# ESC.net
KiCad netlist of a schematic drawn in Altium Designer
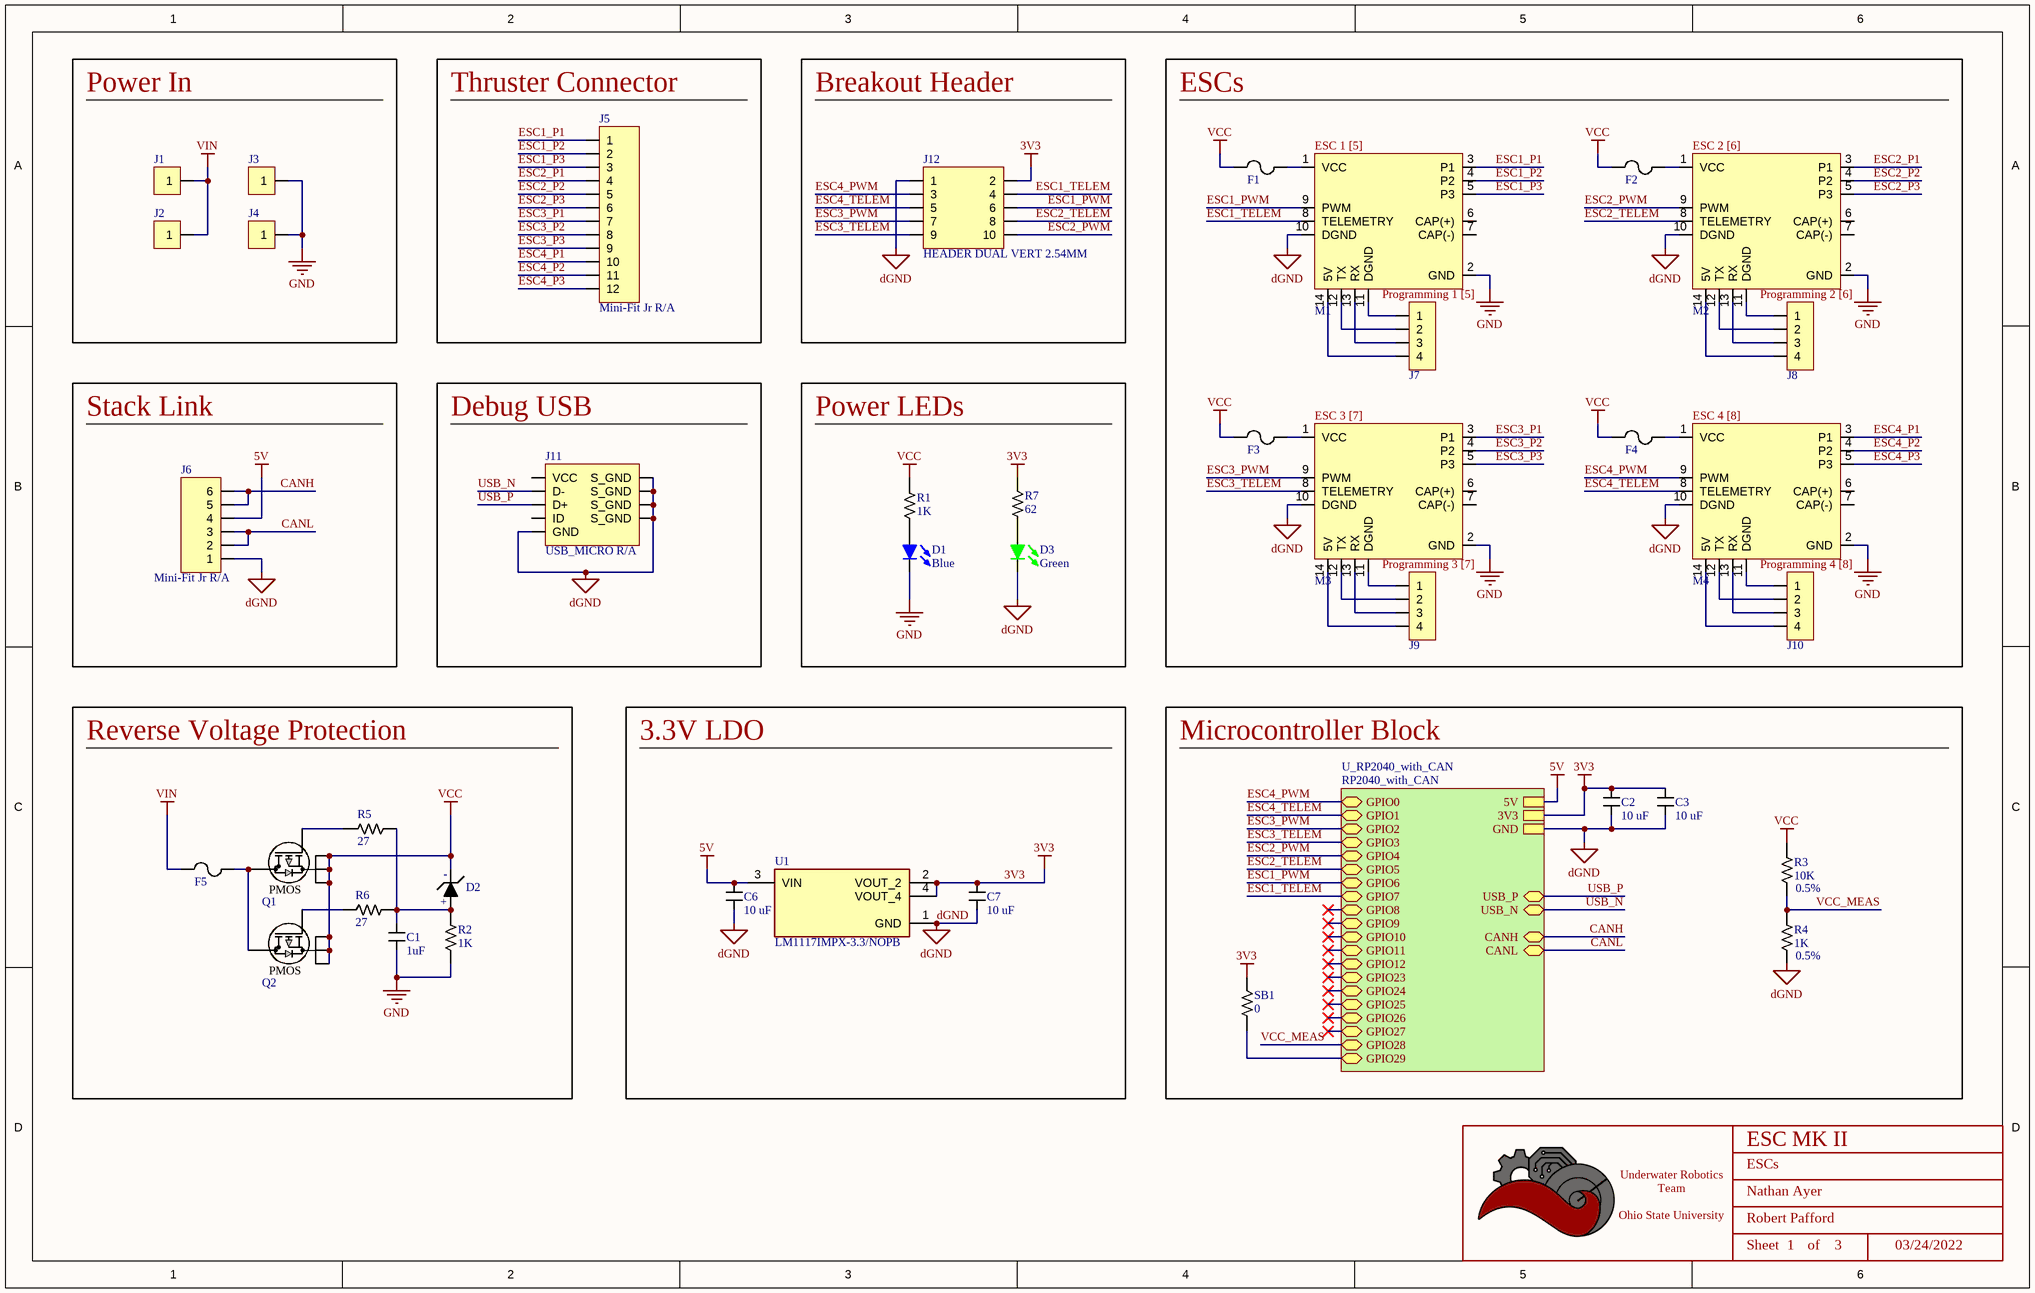
[diagram p0: ESC.SchDoc]

(export (version "E")
  (design (tool "Eeschema 10.0.6"))
  (components
    (comp (ref "*")
      (value "Title_Block")
      (footprint "LOGO")
      (description "UWRT Schematic Title Block Template\r\n\r\nCreated June 2021, Dylan Trainor")
      (libsource (lib "UWRT") (part "Title_Block"))
    )
    (comp (ref "C1")
      (value "1uF")
      (footprint "CAPACITOR_0603")
      (description "Cap 1uF 16V +/-10%\r\nCeramic 0603")
      (fields
        (field (name "TOLERANCE") "+/- 10%")
        (field (name "VOLTAGE") "16V")
        (field (name "MADE BY") "Flip B")
      )
      (libsource (lib "Capacitors") (part "CAPACITOR_1uF_0603"))
    )
    (comp (ref "C2")
      (value "10uF Ceramic 6.3V")
      (footprint "CAPACITOR_0603")
      (description "Cap 10uF 6.3V +/-20%\r\nCeramic 0603")
      (fields
        (field (name "TOLERANCE") "+/- 20%")
        (field (name "VOLTAGE") "6.3V")
        (field (name "VALUE (UF)") "10 uF")
        (field (name "MADE BY") "Flip B")
      )
      (libsource (lib "Capacitors") (part "CAPACITOR_10uF_0603"))
    )
    (comp (ref "C3")
      (value "10uF Ceramic 6.3V")
      (footprint "CAPACITOR_0603")
      (description "Cap 10uF 6.3V +/-20%\r\nCeramic 0603")
      (fields
        (field (name "TOLERANCE") "+/- 20%")
        (field (name "VOLTAGE") "6.3V")
        (field (name "VALUE (UF)") "10 uF")
        (field (name "MADE BY") "Flip B")
      )
      (libsource (lib "Capacitors") (part "CAPACITOR_10uF_0603"))
    )
    (comp (ref "C6")
      (value "10uF Ceramic 6.3V")
      (footprint "CAPACITOR_0603")
      (description "Cap 10uF 6.3V +/-20%\r\nCeramic 0603")
      (fields
        (field (name "TOLERANCE") "+/- 20%")
        (field (name "VOLTAGE") "6.3V")
        (field (name "VALUE (UF)") "10 uF")
        (field (name "MADE BY") "Flip B")
      )
      (libsource (lib "Capacitors") (part "CAPACITOR_10uF_0603"))
    )
    (comp (ref "C7")
      (value "10uF Ceramic 6.3V")
      (footprint "CAPACITOR_0603")
      (description "Cap 10uF 6.3V +/-20%\r\nCeramic 0603")
      (fields
        (field (name "TOLERANCE") "+/- 20%")
        (field (name "VOLTAGE") "6.3V")
        (field (name "VALUE (UF)") "10 uF")
        (field (name "MADE BY") "Flip B")
      )
      (libsource (lib "Capacitors") (part "CAPACITOR_10uF_0603"))
    )
    (comp (ref "D1")
      (value "150060BS75000")
      (footprint "LED_0603")
      (description "LED Blue Vf= 3.2V If = 0.020A\r\n150060BS75000")
      (fields (field (name "COLOR") "Blue") (field (name "MADE BY") "Robert Pafford"))
      (libsource (lib "Diodes") (part "LED_Blue_0603"))
    )
    (comp (ref "D2")
      (value "Zener_Diode_10V_410mW")
      (footprint "SOD-123")
      (description "Zener Diode ¦ 10 V ¦ 410 mW ¦ SOD 123")
      (fields (field (name "POWER") "410mW") (field (name "MADE BY") "Nathan A"))
      (libsource (lib "Diodes") (part "Zener_Diode_10V_410mW"))
    )
    (comp (ref "D3")
      (value "150060GS75000")
      (footprint "LED_0603")
      (description "LED Green Vf= 3.2V If = 0.025A\r\n150060GS75000")
      (fields (field (name "COLOR") "Green") (field (name "MADE BY") "Flip B"))
      (libsource (lib "Diodes") (part "LED_Green_0603_3.2V"))
    )
    (comp (ref "F1")
      (value "0685H9150-01")
      (footprint "0501Series_LTF")
      (description "Bel Fuse  ¦ 15A ¦ 32V DC ¦ SMD ¦ Fast Blow ¦ 1206")
      (fields (field (name "CREATED BY") "Nathan Ayer"))
      (libsource (lib "Fuses") (part "Bel Fuse 15A"))
    )
    (comp (ref "F2")
      (value "0685H9150-01")
      (footprint "0501Series_LTF")
      (description "Bel Fuse  ¦ 15A ¦ 32V DC ¦ SMD ¦ Fast Blow ¦ 1206")
      (fields (field (name "CREATED BY") "Nathan Ayer"))
      (libsource (lib "Fuses") (part "Bel Fuse 15A"))
    )
    (comp (ref "F3")
      (value "0685H9150-01")
      (footprint "0501Series_LTF")
      (description "Bel Fuse  ¦ 15A ¦ 32V DC ¦ SMD ¦ Fast Blow ¦ 1206")
      (fields (field (name "CREATED BY") "Nathan Ayer"))
      (libsource (lib "Fuses") (part "Bel Fuse 15A"))
    )
    (comp (ref "F4")
      (value "0685H9150-01")
      (footprint "0501Series_LTF")
      (description "Bel Fuse  ¦ 15A ¦ 32V DC ¦ SMD ¦ Fast Blow ¦ 1206")
      (fields (field (name "CREATED BY") "Nathan Ayer"))
      (libsource (lib "Fuses") (part "Bel Fuse 15A"))
    )
    (comp (ref "F5")
      (value "1245HC60-RTR")
      (footprint "2-SMD Fuse")
      (description "Eaton  ¦ 60A ¦ 80V DC ¦ SMD ¦ Fast Blow ¦ 2-SMD")
      (fields (field (name "CREATED BY") "Nathan Ayer"))
      (libsource (lib "Fuses") (part "Eaton 60A Fuse"))
    )
    (comp (ref "J1")
      (value "Redcube M4 Term 85A")
      (footprint "Redcube M4 Term 85A")
      (fields (field (name "CREATED BY") "Nahtan Ayer"))
      (libsource (lib "Connectors") (part "Redcube M4 Term 85A"))
    )
    (comp (ref "J2")
      (value "Redcube M4 Term 85A")
      (footprint "Redcube M4 Term 85A")
      (fields (field (name "CREATED BY") "Nahtan Ayer"))
      (libsource (lib "Connectors") (part "Redcube M4 Term 85A"))
    )
    (comp (ref "J3")
      (value "Redcube M4 Term 85A")
      (footprint "Redcube M4 Term 85A")
      (fields (field (name "CREATED BY") "Nahtan Ayer"))
      (libsource (lib "Connectors") (part "Redcube M4 Term 85A"))
    )
    (comp (ref "J4")
      (value "Redcube M4 Term 85A")
      (footprint "Redcube M4 Term 85A")
      (fields (field (name "CREATED BY") "Nahtan Ayer"))
      (libsource (lib "Connectors") (part "Redcube M4 Term 85A"))
    )
    (comp (ref "J5")
      (value "Mini-Fit Jr R/A")
      (footprint "CONN_MOLEX_MINIFIT JR_12 POS_R/A")
      (description "Molex Minifit Jr. 5569 \r\n12 Pos R/A Natural")
      (fields (field (name "MANUFACTURER") "Molex") (field (name "CREATED BY") "Flip B"))
      (libsource (lib "Connectors") (part "CONN_MOLEX_MINIFIT JR_12POS_R/A"))
    )
    (comp (ref "J6")
      (value "Mini-Fit Jr R/A")
      (footprint "CONN_MOLEX_MINIFIT JR_6 POS_R/A")
      (description "Molex Minifit Jr. 5569 \r\n6 Pos R/A Natural")
      (fields (field (name "MANUFACTURER") "Molex") (field (name "CREATED BY") "Flip B"))
      (libsource (lib "Connectors") (part "CONN_MOLEX_MINIFIT JR_6POS_R/A"))
    )
    (comp (ref "J7")
      (value "HEADER VERT 2.54MM")
      (footprint "HEADER_4PIN_2.54MM")
      (description "CONN HEADER VERT 4POS 2.54MM")
      (fields (field (name "MADE BY") "Robert Pafford"))
      (libsource (lib "Connectors") (part "HEADER_4PIN_2.54MM"))
    )
    (comp (ref "J8")
      (value "HEADER VERT 2.54MM")
      (footprint "HEADER_4PIN_2.54MM")
      (description "CONN HEADER VERT 4POS 2.54MM")
      (fields (field (name "MADE BY") "Robert Pafford"))
      (libsource (lib "Connectors") (part "HEADER_4PIN_2.54MM"))
    )
    (comp (ref "J9")
      (value "HEADER VERT 2.54MM")
      (footprint "HEADER_4PIN_2.54MM")
      (description "CONN HEADER VERT 4POS 2.54MM")
      (fields (field (name "MADE BY") "Robert Pafford"))
      (libsource (lib "Connectors") (part "HEADER_4PIN_2.54MM"))
    )
    (comp (ref "J10")
      (value "HEADER VERT 2.54MM")
      (footprint "HEADER_4PIN_2.54MM")
      (description "CONN HEADER VERT 4POS 2.54MM")
      (fields (field (name "MADE BY") "Robert Pafford"))
      (libsource (lib "Connectors") (part "HEADER_4PIN_2.54MM"))
    )
    (comp (ref "J11")
      (value "USB_MICRO R/A")
      (footprint "CONN_MINIUSB")
      (description "Amphenol Micro USB-B\r\nUSB2.0 5 Pin Right Angle SMD")
      (fields (field (name "MANUFACTURER") "Amphenol") (field (name "CREATED BY") "Flip B"))
      (libsource (lib "Connectors") (part "CONN_MICROUSB"))
    )
    (comp (ref "J12")
      (value "HEADER DUAL VERT 2.54MM")
      (footprint "HEADER_2X5PIN_2.54MM")
      (description "CONN HEADER VERT 10POS 2.54MM")
      (fields (field (name "MADE BY") "Robert Pafford"))
      (libsource (lib "Connectors") (part "HEADER_2x5PIN_2.54MM"))
    )
    (comp (ref "M1")
      (value "APD 80F3[X]")
      (footprint "APD 80F3[X]")
      (description "Advanced Power Drives 80F3[X] ESC ¦ 15-35V ¦ 80A")
      (fields
        (field (name "VOLTAGE") "15-35V")
        (field (name "MANUFACTURER") "Advanced Power Drives")
        (field (name "CREATED BY") "Nathan Ayer")
      )
      (libsource (lib "Modules") (part "APD 80F3[X]"))
    )
    (comp (ref "M2")
      (value "APD 80F3[X]")
      (footprint "APD 80F3[X]")
      (description "Advanced Power Drives 80F3[X] ESC ¦ 15-35V ¦ 80A")
      (fields
        (field (name "VOLTAGE") "15-35V")
        (field (name "MANUFACTURER") "Advanced Power Drives")
        (field (name "CREATED BY") "Nathan Ayer")
      )
      (libsource (lib "Modules") (part "APD 80F3[X]"))
    )
    (comp (ref "M3")
      (value "APD 80F3[X]")
      (footprint "APD 80F3[X]")
      (description "Advanced Power Drives 80F3[X] ESC ¦ 15-35V ¦ 80A")
      (fields
        (field (name "VOLTAGE") "15-35V")
        (field (name "MANUFACTURER") "Advanced Power Drives")
        (field (name "CREATED BY") "Nathan Ayer")
      )
      (libsource (lib "Modules") (part "APD 80F3[X]"))
    )
    (comp (ref "M4")
      (value "APD 80F3[X]")
      (footprint "APD 80F3[X]")
      (description "Advanced Power Drives 80F3[X] ESC ¦ 15-35V ¦ 80A")
      (fields
        (field (name "VOLTAGE") "15-35V")
        (field (name "MANUFACTURER") "Advanced Power Drives")
        (field (name "CREATED BY") "Nathan Ayer")
      )
      (libsource (lib "Modules") (part "APD 80F3[X]"))
    )
    (comp (ref "Q1")
      (value "MOSFET P-Ch 30V 60A SO-8")
      (footprint "MOSFET_7DP-T1-GE3_VIS")
      (description "P-Channel 30 V 60A (Tc) 65.8W (Tc) Surface Mount PowerPAK® SO-8")
      (fields
        (field (name "MANUFACTURER_PART_NUMBER") "SIR167DP-T1-GE3")
        (field (name "COPYRIGHT") "Copyright (C) 2022 Ultra Librarian. All rights reserved.")
      )
      (libsource (lib "Transistors") (part "SIR167DP-T1-GE3"))
    )
    (comp (ref "Q2")
      (value "MOSFET P-Ch 30V 60A SO-8")
      (footprint "MOSFET_7DP-T1-GE3_VIS")
      (description "P-Channel 30 V 60A (Tc) 65.8W (Tc) Surface Mount PowerPAK® SO-8")
      (fields
        (field (name "MANUFACTURER_PART_NUMBER") "SIR167DP-T1-GE3")
        (field (name "COPYRIGHT") "Copyright (C) 2022 Ultra Librarian. All rights reserved.")
      )
      (libsource (lib "Transistors") (part "SIR167DP-T1-GE3"))
    )
    (comp (ref "R1")
      (value "1k Ohm 5% 1/8W")
      (footprint "RESISTOR_0603")
      (description "RES 1k OHM 5% 1/8W 0603")
      (fields
        (field (name "TOLERANCE") "+/- 5%")
        (field (name "VALUE  (OHMS)") "1K")
        (field (name "MADE BY") "Robert Pafford")
      )
      (libsource (lib "Resistors") (part "RESISTOR_1K_0603"))
    )
    (comp (ref "R2")
      (value "1k Ohm 5% 1/8W")
      (footprint "RESISTOR_0603")
      (description "RES 1k OHM 5% 1/8W 0603")
      (fields
        (field (name "TOLERANCE") "+/- 5%")
        (field (name "VALUE  (OHMS)") "1K")
        (field (name "MADE BY") "Robert Pafford")
      )
      (libsource (lib "Resistors") (part "RESISTOR_1K_0603"))
    )
    (comp (ref "R3")
      (value "10k Ohm 0.5% 1/10W")
      (footprint "RESISTOR_0603")
      (description "RES 10k OHM 0.5% 1/10W 0603")
      (fields
        (field (name "TOLERANCE") "+/- 0.5%")
        (field (name "VALUE  (OHMS)") "10K")
        (field (name "MADE BY") "Robert Pafford")
      )
      (libsource (lib "Resistors") (part "RESISTOR_10K_0.5%_0603"))
    )
    (comp (ref "R4")
      (value "1k Ohm 5% 1/10W")
      (footprint "RESISTOR_0603")
      (description "RES 1k OHM 0.5% 1/10W 0603")
      (fields
        (field (name "TOLERANCE") "+/- 0.5%")
        (field (name "VALUE  (OHMS)") "1K")
        (field (name "MADE BY") "Robert Pafford")
      )
      (libsource (lib "Resistors") (part "RESISTOR_1K_0.5%_0603"))
    )
    (comp (ref "R5")
      (value "27 Ohm 5% 1/8W")
      (footprint "RESISTOR_0603")
      (description "RES 27 OHM 5% 1/8W 0603")
      (fields
        (field (name "TOLERANCE") "+/- 5%")
        (field (name "VALUE  (OHMS)") "27")
        (field (name "MADE BY") "Robert Pafford")
      )
      (libsource (lib "Resistors") (part "RESISTOR_27_0603"))
    )
    (comp (ref "R6")
      (value "27 Ohm 5% 1/8W")
      (footprint "RESISTOR_0603")
      (description "RES 27 OHM 5% 1/8W 0603")
      (fields
        (field (name "TOLERANCE") "+/- 5%")
        (field (name "VALUE  (OHMS)") "27")
        (field (name "MADE BY") "Robert Pafford")
      )
      (libsource (lib "Resistors") (part "RESISTOR_27_0603"))
    )
    (comp (ref "R7")
      (value "62 Ohm 1% 1/4W")
      (footprint "RESISTOR_0603")
      (description "RES SMD 62 OHM 1% 1/4W 0603")
      (fields
        (field (name "TOLERANCE") "+/- 1%")
        (field (name "VALUE  (OHMS)") "62")
        (field (name "MADE BY") "Robert Pafford")
      )
      (libsource (lib "Resistors") (part "RESISTOR_62_0603"))
    )
    (comp (ref "SB1")
      (value "0 Ohm Jumper No Fit")
      (footprint "RESISTOR_0603")
      (description "0 Ohm Jumper No Fit for Solder Bridge")
      (fields (field (name "VALUE  (OHMS)") "0") (field (name "MADE BY") "Robert Pafford"))
      (libsource (lib "Resistors") (part "JUMPER_0_0603"))
    )
    (comp (ref "U1")
      (value "LM1117IMPX-3.3/NOPB")
      (footprint "SOT-223-4")
      (description "800-mA 15-V linear voltage regulator 4-SOT-223 -40 to 125")
      (fields (field (name "MF") "Texas Instruments"))
      (libsource (lib "Integrated Circuits") (part "LM1117IMPX-3.3/NOPB"))
    )
  )
  (nets
    (net (code "1") (name "/CANH") (class "Default")
      (node (ref "J6") (pin "5") (pinfunction "5_5") (pintype "passive"))
      (node (ref "J6") (pin "6") (pinfunction "6_6") (pintype "passive"))
    )
    (net (code "2") (name "/CANL") (class "Default")
      (node (ref "J6") (pin "2") (pinfunction "2_2") (pintype "passive"))
      (node (ref "J6") (pin "3") (pinfunction "3_3") (pintype "passive"))
    )
    (net (code "3") (name "/ESC1_P1") (class "Default")
      (node (ref "J5") (pin "1") (pinfunction "1_1") (pintype "passive"))
      (node (ref "M1") (pin "3") (pinfunction "P1_3") (pintype "passive"))
    )
    (net (code "4") (name "/ESC1_P2") (class "Default")
      (node (ref "J5") (pin "2") (pinfunction "2_2") (pintype "passive"))
      (node (ref "M1") (pin "4") (pinfunction "P2_4") (pintype "passive"))
    )
    (net (code "5") (name "/ESC1_P3") (class "Default")
      (node (ref "J5") (pin "3") (pinfunction "3_3") (pintype "passive"))
      (node (ref "M1") (pin "5") (pinfunction "P3_5") (pintype "passive"))
    )
    (net (code "6") (name "/ESC1_PWM") (class "Default")
      (node (ref "J12") (pin "6") (pinfunction "6_6") (pintype "passive"))
      (node (ref "M1") (pin "9") (pinfunction "PWM_9") (pintype "passive"))
    )
    (net (code "7") (name "/ESC1_TELEM") (class "Default")
      (node (ref "J12") (pin "4") (pinfunction "4_4") (pintype "passive"))
      (node (ref "M1") (pin "8") (pinfunction "TELEMETRY_8") (pintype "passive"))
    )
    (net (code "8") (name "/ESC2_P1") (class "Default")
      (node (ref "J5") (pin "4") (pinfunction "4_4") (pintype "passive"))
      (node (ref "M2") (pin "3") (pinfunction "P1_3") (pintype "passive"))
    )
    (net (code "9") (name "/ESC2_P2") (class "Default")
      (node (ref "J5") (pin "5") (pinfunction "5_5") (pintype "passive"))
      (node (ref "M2") (pin "4") (pinfunction "P2_4") (pintype "passive"))
    )
    (net (code "10") (name "/ESC2_P3") (class "Default")
      (node (ref "J5") (pin "6") (pinfunction "6_6") (pintype "passive"))
      (node (ref "M2") (pin "5") (pinfunction "P3_5") (pintype "passive"))
    )
    (net (code "11") (name "/ESC2_PWM") (class "Default")
      (node (ref "J12") (pin "10") (pinfunction "10_10") (pintype "passive"))
      (node (ref "M2") (pin "9") (pinfunction "PWM_9") (pintype "passive"))
    )
    (net (code "12") (name "/ESC2_TELEM") (class "Default")
      (node (ref "J12") (pin "8") (pinfunction "8_8") (pintype "passive"))
      (node (ref "M2") (pin "8") (pinfunction "TELEMETRY_8") (pintype "passive"))
    )
    (net (code "13") (name "/ESC3_P1") (class "Default")
      (node (ref "J5") (pin "7") (pinfunction "7_7") (pintype "passive"))
      (node (ref "M3") (pin "3") (pinfunction "P1_3") (pintype "passive"))
    )
    (net (code "14") (name "/ESC3_P2") (class "Default")
      (node (ref "J5") (pin "8") (pinfunction "8_8") (pintype "passive"))
      (node (ref "M3") (pin "4") (pinfunction "P2_4") (pintype "passive"))
    )
    (net (code "15") (name "/ESC3_P3") (class "Default")
      (node (ref "J5") (pin "9") (pinfunction "9_9") (pintype "passive"))
      (node (ref "M3") (pin "5") (pinfunction "P3_5") (pintype "passive"))
    )
    (net (code "16") (name "/ESC3_PWM") (class "Default")
      (node (ref "J12") (pin "7") (pinfunction "7_7") (pintype "passive"))
      (node (ref "M3") (pin "9") (pinfunction "PWM_9") (pintype "passive"))
    )
    (net (code "17") (name "/ESC3_TELEM") (class "Default")
      (node (ref "J12") (pin "9") (pinfunction "9_9") (pintype "passive"))
      (node (ref "M3") (pin "8") (pinfunction "TELEMETRY_8") (pintype "passive"))
    )
    (net (code "18") (name "/ESC4_P1") (class "Default")
      (node (ref "J5") (pin "10") (pinfunction "10_10") (pintype "passive"))
      (node (ref "M4") (pin "3") (pinfunction "P1_3") (pintype "passive"))
    )
    (net (code "19") (name "/ESC4_P2") (class "Default")
      (node (ref "J5") (pin "11") (pinfunction "11_11") (pintype "passive"))
      (node (ref "M4") (pin "4") (pinfunction "P2_4") (pintype "passive"))
    )
    (net (code "20") (name "/ESC4_P3") (class "Default")
      (node (ref "J5") (pin "12") (pinfunction "12_12") (pintype "passive"))
      (node (ref "M4") (pin "5") (pinfunction "P3_5") (pintype "passive"))
    )
    (net (code "21") (name "/ESC4_PWM") (class "Default")
      (node (ref "J12") (pin "3") (pinfunction "3_3") (pintype "passive"))
      (node (ref "M4") (pin "9") (pinfunction "PWM_9") (pintype "passive"))
    )
    (net (code "22") (name "/ESC4_TELEM") (class "Default")
      (node (ref "J12") (pin "5") (pinfunction "5_5") (pintype "passive"))
      (node (ref "M4") (pin "8") (pinfunction "TELEMETRY_8") (pintype "passive"))
    )
    (net (code "33") (name "/GPIO29") (class "Default")
      (node (ref "SB1") (pin "1") (pinfunction "1_1") (pintype "passive"))
    )
    (net (code "34") (name "/USB_N") (class "Default")
      (node (ref "J11") (pin "2") (pinfunction "D-_2") (pintype "passive"))
    )
    (net (code "35") (name "/USB_P") (class "Default")
      (node (ref "J11") (pin "3") (pinfunction "D+_3") (pintype "passive"))
    )
    (net (code "36") (name "/VCC_MEAS") (class "Default")
      (node (ref "R3") (pin "2") (pinfunction "2_2") (pintype "passive"))
      (node (ref "R4") (pin "1") (pinfunction "1_1") (pintype "passive"))
    )
    (net (code "37") (name "3V3") (class "Default")
      (node (ref "C2") (pin "1") (pinfunction "1_1") (pintype "passive"))
      (node (ref "C3") (pin "1") (pinfunction "1_1") (pintype "passive"))
      (node (ref "C7") (pin "1") (pinfunction "1_1") (pintype "passive"))
      (node (ref "J12") (pin "2") (pinfunction "2_2") (pintype "passive"))
      (node (ref "R7") (pin "2") (pinfunction "2_2") (pintype "passive"))
      (node (ref "SB1") (pin "2") (pinfunction "2_2") (pintype "passive"))
      (node (ref "U1") (pin "2") (pinfunction "VOUT_2_2") (pintype "power_in"))
      (node (ref "U1") (pin "4") (pinfunction "VOUT_4_4") (pintype "power_in"))
    )
    (net (code "38") (name "5V") (class "Default")
      (node (ref "C6") (pin "1") (pinfunction "1_1") (pintype "passive"))
      (node (ref "J6") (pin "4") (pinfunction "4_4") (pintype "passive"))
      (node (ref "U1") (pin "3") (pinfunction "VIN_3") (pintype "power_in"))
    )
    (net (code "39") (name "GND") (class "Default")
      (node (ref "C1") (pin "1") (pinfunction "1_1") (pintype "passive"))
      (node (ref "D1") (pin "2") (pinfunction "2_2") (pintype "passive"))
      (node (ref "J3") (pin "1") (pinfunction "1_1") (pintype "passive"))
      (node (ref "J4") (pin "1") (pinfunction "1_1") (pintype "passive"))
      (node (ref "M1") (pin "2") (pinfunction "GND_2") (pintype "passive"))
      (node (ref "M2") (pin "2") (pinfunction "GND_2") (pintype "passive"))
      (node (ref "M3") (pin "2") (pinfunction "GND_2") (pintype "passive"))
      (node (ref "M4") (pin "2") (pinfunction "GND_2") (pintype "passive"))
      (node (ref "R2") (pin "2") (pinfunction "2_2") (pintype "passive"))
    )
    (net (code "40") (name "Net-(C1-Pad2)") (class "Default")
      (node (ref "C1") (pin "2") (pinfunction "2_2") (pintype "passive"))
      (node (ref "D2") (pin "1") (pinfunction "1_1") (pintype "passive"))
      (node (ref "R2") (pin "1") (pinfunction "1_1") (pintype "passive"))
      (node (ref "R5") (pin "2") (pinfunction "2_2") (pintype "passive"))
      (node (ref "R6") (pin "1") (pinfunction "1_1") (pintype "passive"))
    )
    (net (code "41") (name "Net-(D1-Pad1)") (class "Default")
      (node (ref "D1") (pin "1") (pinfunction "1_1") (pintype "passive"))
      (node (ref "R1") (pin "2") (pinfunction "2_2") (pintype "passive"))
    )
    (net (code "42") (name "Net-(D3-Pad1)") (class "Default")
      (node (ref "D3") (pin "1") (pinfunction "1_1") (pintype "passive"))
      (node (ref "R7") (pin "1") (pinfunction "1_1") (pintype "passive"))
    )
    (net (code "43") (name "Net-(F5-Pad2)") (class "Default")
      (node (ref "F5") (pin "2") (pinfunction "2_2") (pintype "passive"))
      (node (ref "Q1") (pin "D") (pinfunction "D_D") (pintype "passive"))
      (node (ref "Q2") (pin "D") (pinfunction "D_D") (pintype "passive"))
    )
    (net (code "44") (name "Net-(J7-Pad1)") (class "Default")
      (node (ref "J7") (pin "1") (pinfunction "1_1") (pintype "passive"))
      (node (ref "M1") (pin "11") (pinfunction "DGND_11") (pintype "passive"))
    )
    (net (code "45") (name "Net-(J8-Pad1)") (class "Default")
      (node (ref "J8") (pin "1") (pinfunction "1_1") (pintype "passive"))
      (node (ref "M2") (pin "11") (pinfunction "DGND_11") (pintype "passive"))
    )
    (net (code "46") (name "Net-(J9-Pad1)") (class "Default")
      (node (ref "J9") (pin "1") (pinfunction "1_1") (pintype "passive"))
      (node (ref "M3") (pin "11") (pinfunction "DGND_11") (pintype "passive"))
    )
    (net (code "47") (name "Net-(J10-Pad1)") (class "Default")
      (node (ref "J10") (pin "1") (pinfunction "1_1") (pintype "passive"))
      (node (ref "M4") (pin "11") (pinfunction "DGND_11") (pintype "passive"))
    )
    (net (code "48") (name "Net-(M1-5V)") (class "Default")
      (node (ref "J7") (pin "4") (pinfunction "4_4") (pintype "passive"))
      (node (ref "M1") (pin "14") (pinfunction "5V_14") (pintype "passive"))
    )
    (net (code "49") (name "Net-(M1-RX)") (class "Default")
      (node (ref "J7") (pin "3") (pinfunction "3_3") (pintype "passive"))
      (node (ref "M1") (pin "13") (pinfunction "RX_13") (pintype "passive"))
    )
    (net (code "50") (name "Net-(M1-TX)") (class "Default")
      (node (ref "J7") (pin "2") (pinfunction "2_2") (pintype "passive"))
      (node (ref "M1") (pin "12") (pinfunction "TX_12") (pintype "passive"))
    )
    (net (code "51") (name "Net-(M1-VCC)") (class "Default")
      (node (ref "F1") (pin "2") (pinfunction "2_2") (pintype "passive"))
      (node (ref "M1") (pin "1") (pinfunction "VCC_1") (pintype "passive"))
    )
    (net (code "52") (name "Net-(M2-5V)") (class "Default")
      (node (ref "J8") (pin "4") (pinfunction "4_4") (pintype "passive"))
      (node (ref "M2") (pin "14") (pinfunction "5V_14") (pintype "passive"))
    )
    (net (code "53") (name "Net-(M2-RX)") (class "Default")
      (node (ref "J8") (pin "3") (pinfunction "3_3") (pintype "passive"))
      (node (ref "M2") (pin "13") (pinfunction "RX_13") (pintype "passive"))
    )
    (net (code "54") (name "Net-(M2-TX)") (class "Default")
      (node (ref "J8") (pin "2") (pinfunction "2_2") (pintype "passive"))
      (node (ref "M2") (pin "12") (pinfunction "TX_12") (pintype "passive"))
    )
    (net (code "55") (name "Net-(M2-VCC)") (class "Default")
      (node (ref "F2") (pin "2") (pinfunction "2_2") (pintype "passive"))
      (node (ref "M2") (pin "1") (pinfunction "VCC_1") (pintype "passive"))
    )
    (net (code "56") (name "Net-(M3-5V)") (class "Default")
      (node (ref "J9") (pin "4") (pinfunction "4_4") (pintype "passive"))
      (node (ref "M3") (pin "14") (pinfunction "5V_14") (pintype "passive"))
    )
    (net (code "57") (name "Net-(M3-RX)") (class "Default")
      (node (ref "J9") (pin "3") (pinfunction "3_3") (pintype "passive"))
      (node (ref "M3") (pin "13") (pinfunction "RX_13") (pintype "passive"))
    )
    (net (code "58") (name "Net-(M3-TX)") (class "Default")
      (node (ref "J9") (pin "2") (pinfunction "2_2") (pintype "passive"))
      (node (ref "M3") (pin "12") (pinfunction "TX_12") (pintype "passive"))
    )
    (net (code "59") (name "Net-(M3-VCC)") (class "Default")
      (node (ref "F3") (pin "2") (pinfunction "2_2") (pintype "passive"))
      (node (ref "M3") (pin "1") (pinfunction "VCC_1") (pintype "passive"))
    )
    (net (code "60") (name "Net-(M4-5V)") (class "Default")
      (node (ref "J10") (pin "4") (pinfunction "4_4") (pintype "passive"))
      (node (ref "M4") (pin "14") (pinfunction "5V_14") (pintype "passive"))
    )
    (net (code "61") (name "Net-(M4-RX)") (class "Default")
      (node (ref "J10") (pin "3") (pinfunction "3_3") (pintype "passive"))
      (node (ref "M4") (pin "13") (pinfunction "RX_13") (pintype "passive"))
    )
    (net (code "62") (name "Net-(M4-TX)") (class "Default")
      (node (ref "J10") (pin "2") (pinfunction "2_2") (pintype "passive"))
      (node (ref "M4") (pin "12") (pinfunction "TX_12") (pintype "passive"))
    )
    (net (code "63") (name "Net-(M4-VCC)") (class "Default")
      (node (ref "F4") (pin "2") (pinfunction "2_2") (pintype "passive"))
      (node (ref "M4") (pin "1") (pinfunction "VCC_1") (pintype "passive"))
    )
    (net (code "64") (name "Net-(Q1-G)") (class "Default")
      (node (ref "Q1") (pin "4") (pinfunction "G_4") (pintype "passive"))
      (node (ref "R5") (pin "1") (pinfunction "1_1") (pintype "passive"))
    )
    (net (code "65") (name "Net-(Q2-G)") (class "Default")
      (node (ref "Q2") (pin "4") (pinfunction "G_4") (pintype "passive"))
      (node (ref "R6") (pin "2") (pinfunction "2_2") (pintype "passive"))
    )
    (net (code "66") (name "VCC") (class "Default")
      (node (ref "D2") (pin "2") (pinfunction "2_2") (pintype "passive"))
      (node (ref "F1") (pin "1") (pinfunction "1_1") (pintype "passive"))
      (node (ref "F2") (pin "1") (pinfunction "1_1") (pintype "passive"))
      (node (ref "F3") (pin "1") (pinfunction "1_1") (pintype "passive"))
      (node (ref "F4") (pin "1") (pinfunction "1_1") (pintype "passive"))
      (node (ref "Q1") (pin "1") (pinfunction "S_1") (pintype "passive"))
      (node (ref "Q1") (pin "2") (pinfunction "S_2") (pintype "passive"))
      (node (ref "Q1") (pin "3") (pinfunction "S_3") (pintype "passive"))
      (node (ref "Q2") (pin "1") (pinfunction "S_1") (pintype "passive"))
      (node (ref "Q2") (pin "2") (pinfunction "S_2") (pintype "passive"))
      (node (ref "Q2") (pin "3") (pinfunction "S_3") (pintype "passive"))
      (node (ref "R1") (pin "1") (pinfunction "1_1") (pintype "passive"))
      (node (ref "R3") (pin "1") (pinfunction "1_1") (pintype "passive"))
    )
    (net (code "67") (name "VIN") (class "Default")
      (node (ref "F5") (pin "1") (pinfunction "1_1") (pintype "passive"))
      (node (ref "J1") (pin "1") (pinfunction "1_1") (pintype "passive"))
      (node (ref "J2") (pin "1") (pinfunction "1_1") (pintype "passive"))
    )
    (net (code "68") (name "dGND") (class "Default")
      (node (ref "C2") (pin "2") (pinfunction "2_2") (pintype "passive"))
      (node (ref "C3") (pin "2") (pinfunction "2_2") (pintype "passive"))
      (node (ref "C6") (pin "2") (pinfunction "2_2") (pintype "passive"))
      (node (ref "C7") (pin "2") (pinfunction "2_2") (pintype "passive"))
      (node (ref "D3") (pin "2") (pinfunction "2_2") (pintype "passive"))
      (node (ref "J11") (pin "5") (pinfunction "GND_5") (pintype "passive"))
      (node (ref "J11") (pin "6") (pinfunction "S_GND_6") (pintype "passive"))
      (node (ref "J11") (pin "7") (pinfunction "S_GND_7") (pintype "passive"))
      (node (ref "J11") (pin "8") (pinfunction "S_GND_8") (pintype "passive"))
      (node (ref "J11") (pin "9") (pinfunction "S_GND_9") (pintype "passive"))
      (node (ref "J12") (pin "1") (pinfunction "1_1") (pintype "passive"))
      (node (ref "J6") (pin "1") (pinfunction "1_1") (pintype "passive"))
      (node (ref "M1") (pin "10") (pinfunction "DGND_10") (pintype "passive"))
      (node (ref "M2") (pin "10") (pinfunction "DGND_10") (pintype "passive"))
      (node (ref "M3") (pin "10") (pinfunction "DGND_10") (pintype "passive"))
      (node (ref "M4") (pin "10") (pinfunction "DGND_10") (pintype "passive"))
      (node (ref "R4") (pin "2") (pinfunction "2_2") (pintype "passive"))
      (node (ref "U1") (pin "1") (pinfunction "GND_1") (pintype "power_in"))
    )
    (net (code "69") (name "unconnected-(J11-ID-Pad4)") (class "Default")
      (node (ref "J11") (pin "4") (pinfunction "ID_4") (pintype "passive"))
    )
    (net (code "70") (name "unconnected-(J11-VCC-Pad1)") (class "Default")
      (node (ref "J11") (pin "1") (pinfunction "VCC_1") (pintype "passive"))
    )
    (net (code "71") (name "unconnected-(M1-CAP(+)-Pad6)") (class "Default")
      (node (ref "M1") (pin "6") (pinfunction "CAP(+)_6") (pintype "passive"))
    )
    (net (code "72") (name "unconnected-(M1-CAP(-)-Pad7)") (class "Default")
      (node (ref "M1") (pin "7") (pinfunction "CAP(-)_7") (pintype "passive"))
    )
    (net (code "73") (name "unconnected-(M2-CAP(+)-Pad6)") (class "Default")
      (node (ref "M2") (pin "6") (pinfunction "CAP(+)_6") (pintype "passive"))
    )
    (net (code "74") (name "unconnected-(M2-CAP(-)-Pad7)") (class "Default")
      (node (ref "M2") (pin "7") (pinfunction "CAP(-)_7") (pintype "passive"))
    )
    (net (code "75") (name "unconnected-(M3-CAP(+)-Pad6)") (class "Default")
      (node (ref "M3") (pin "6") (pinfunction "CAP(+)_6") (pintype "passive"))
    )
    (net (code "76") (name "unconnected-(M3-CAP(-)-Pad7)") (class "Default")
      (node (ref "M3") (pin "7") (pinfunction "CAP(-)_7") (pintype "passive"))
    )
    (net (code "77") (name "unconnected-(M4-CAP(+)-Pad6)") (class "Default")
      (node (ref "M4") (pin "6") (pinfunction "CAP(+)_6") (pintype "passive"))
    )
    (net (code "78") (name "unconnected-(M4-CAP(-)-Pad7)") (class "Default")
      (node (ref "M4") (pin "7") (pinfunction "CAP(-)_7") (pintype "passive"))
    )
  )
)
